# IO_Boardv2_301115.net
KiCad netlist of a schematic drawn in Altium Designer
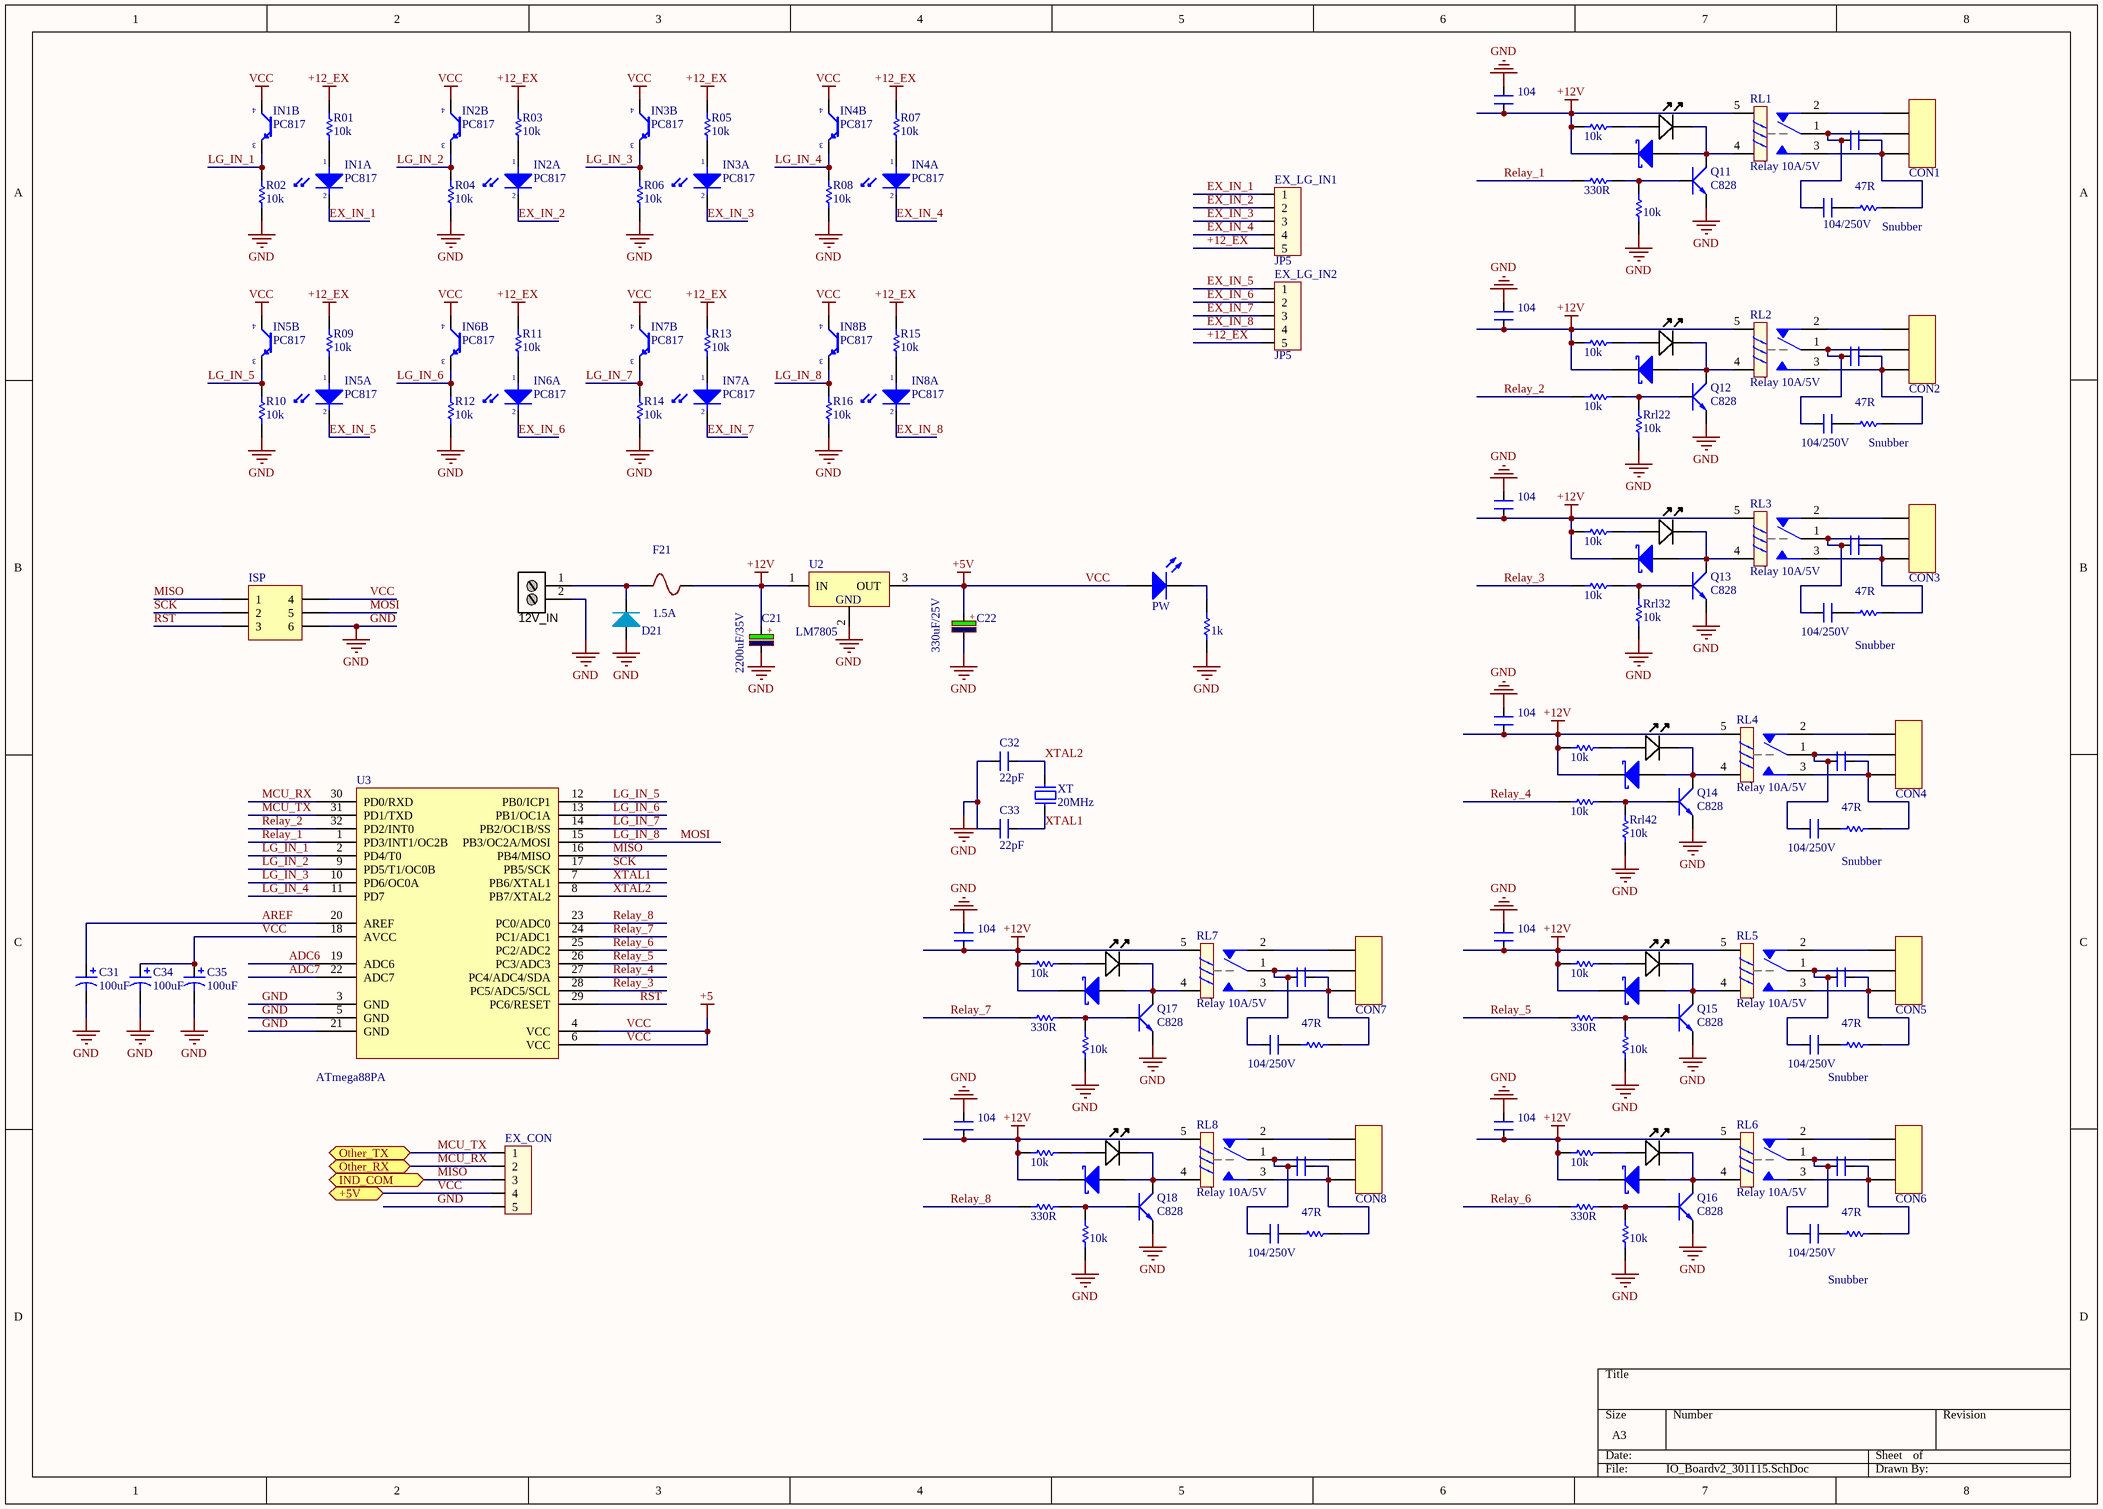
[diagram p0: IO_Boardv2_301115.SchDoc]

(export (version "E")
  (design (tool "Eeschema 10.0.6"))
  (components
    (comp (ref "12V_IN")
      (value "Stackable ScrewTerm")
      (footprint "2P_PCB_ScrewTerm_200mil")
      (description "Terminal Block Screw Type THT 2-Position 3.81mm pitch")
      (libsource (lib "PBL - Connectors") (part "2P_ScrewTerm_90S_3.81MM"))
    )
    (comp (ref "C21")
      (value "2200uF/35V")
      (footprint "heromap:CP_1000uF_25V")
      (description "Cap 1000uF/16V - 220uF/50V")
      (libsource (lib "heromap") (part "CP4"))
    )
    (comp (ref "C22")
      (value "330uF/25V")
      (footprint "heromap:CP1.5/3.4")
      (description "Cap 1000uF/16V - 220uF/50V")
      (libsource (lib "heromap") (part "CP4"))
    )
    (comp (ref "C31")
      (value "100uF")
      (footprint "CAPC2012N_F")
      (fields (field (name "Comment") "Cap"))
      (libsource (lib "Tuan") (part "Cap"))
    )
    (comp (ref "C32")
      (value "22pF")
      (footprint "CAPC1608N")
      (fields (field (name "Comment") "CAP NP"))
      (libsource (lib "Tuan") (part "CAP NP"))
    )
    (comp (ref "C33")
      (value "22pF")
      (footprint "CAPC1608N")
      (fields (field (name "Comment") "CAP NP"))
      (libsource (lib "Tuan") (part "CAP NP"))
    )
    (comp (ref "C34")
      (value "100uF")
      (footprint "CAPC2012N_F")
      (fields (field (name "Comment") "Cap"))
      (libsource (lib "Tuan") (part "Cap"))
    )
    (comp (ref "C35")
      (value "100uF")
      (footprint "CAPC2012N_F")
      (fields (field (name "Comment") "Cap"))
      (libsource (lib "Tuan") (part "Cap"))
    )
    (comp (ref "CON1")
      (value "3P_ScrewTerm_200mil")
      (footprint "3P_ScrewTerm_200mil")
      (libsource (lib "Tuan") (part "3P_ScrewTerm_200mil"))
    )
    (comp (ref "CON2")
      (value "3P_ScrewTerm_200mil")
      (footprint "3P_ScrewTerm_200mil")
      (libsource (lib "Tuan") (part "3P_ScrewTerm_200mil"))
    )
    (comp (ref "CON3")
      (value "3P_ScrewTerm_200mil")
      (footprint "3P_ScrewTerm_200mil")
      (libsource (lib "Tuan") (part "3P_ScrewTerm_200mil"))
    )
    (comp (ref "CON4")
      (value "3P_ScrewTerm_200mil")
      (footprint "3P_ScrewTerm_200mil")
      (libsource (lib "Tuan") (part "3P_ScrewTerm_200mil"))
    )
    (comp (ref "CON5")
      (value "3P_ScrewTerm_200mil")
      (footprint "3P_ScrewTerm_200mil")
      (libsource (lib "Tuan") (part "3P_ScrewTerm_200mil"))
    )
    (comp (ref "CON6")
      (value "3P_ScrewTerm_200mil")
      (footprint "3P_ScrewTerm_200mil")
      (libsource (lib "Tuan") (part "3P_ScrewTerm_200mil"))
    )
    (comp (ref "CON7")
      (value "3P_ScrewTerm_200mil")
      (footprint "3P_ScrewTerm_200mil")
      (libsource (lib "Tuan") (part "3P_ScrewTerm_200mil"))
    )
    (comp (ref "CON8")
      (value "3P_ScrewTerm_200mil")
      (footprint "3P_ScrewTerm_200mil")
      (libsource (lib "Tuan") (part "3P_ScrewTerm_200mil"))
    )
    (comp (ref "Crl1")
      (value "104")
      (footprint "CAPC2012N_F")
      (fields (field (name "Comment") "CAP NP"))
      (libsource (lib "Tuan") (part "CAP NP"))
    )
    (comp (ref "Crl2")
      (value "104")
      (footprint "CAPC2012N_F")
      (fields (field (name "Comment") "CAP NP"))
      (libsource (lib "Tuan") (part "CAP NP"))
    )
    (comp (ref "Crl3")
      (value "104")
      (footprint "CAPC2012N_F")
      (fields (field (name "Comment") "CAP NP"))
      (libsource (lib "Tuan") (part "CAP NP"))
    )
    (comp (ref "Crl4")
      (value "104")
      (footprint "CAPC2012N_F")
      (fields (field (name "Comment") "CAP NP"))
      (libsource (lib "Tuan") (part "CAP NP"))
    )
    (comp (ref "Crl5")
      (value "104")
      (footprint "CAPC2012N_F")
      (fields (field (name "Comment") "CAP NP"))
      (libsource (lib "Tuan") (part "CAP NP"))
    )
    (comp (ref "Crl6")
      (value "104")
      (footprint "CAPC2012N_F")
      (fields (field (name "Comment") "CAP NP"))
      (libsource (lib "Tuan") (part "CAP NP"))
    )
    (comp (ref "Crl7")
      (value "104")
      (footprint "CAPC2012N_F")
      (fields (field (name "Comment") "CAP NP"))
      (libsource (lib "Tuan") (part "CAP NP"))
    )
    (comp (ref "Crl8")
      (value "104")
      (footprint "CAPC2012N_F")
      (fields (field (name "Comment") "CAP NP"))
      (libsource (lib "Tuan") (part "CAP NP"))
    )
    (comp (ref "Csub1")
      (value "104/250V")
      (footprint "CAPMF12.5x4.5x9.0x10mmLS")
      (fields (field (name "Comment") "CAP NP"))
      (libsource (lib "Tuan") (part "CAP NP"))
    )
    (comp (ref "Csub2")
      (value "104/250V")
      (footprint "CAPMF12.5x4.5x9.0x10mmLS")
      (fields (field (name "Comment") "CAP NP"))
      (libsource (lib "Tuan") (part "CAP NP"))
    )
    (comp (ref "Csub3")
      (value "104/250V")
      (footprint "CAPMF12.5x4.5x9.0x10mmLS")
      (fields (field (name "Comment") "CAP NP"))
      (libsource (lib "Tuan") (part "CAP NP"))
    )
    (comp (ref "Csub4")
      (value "104/250V")
      (footprint "CAPMF12.5x4.5x9.0x10mmLS")
      (fields (field (name "Comment") "CAP NP"))
      (libsource (lib "Tuan") (part "CAP NP"))
    )
    (comp (ref "Csub5")
      (value "104/250V")
      (footprint "CAPMF12.5x4.5x9.0x10mmLS")
      (fields (field (name "Comment") "CAP NP"))
      (libsource (lib "Tuan") (part "CAP NP"))
    )
    (comp (ref "Csub6")
      (value "104/250V")
      (footprint "CAPMF12.5x4.5x9.0x10mmLS")
      (fields (field (name "Comment") "CAP NP"))
      (libsource (lib "Tuan") (part "CAP NP"))
    )
    (comp (ref "Csub7")
      (value "104/250V")
      (footprint "CAPMF12.5x4.5x9.0x10mmLS")
      (fields (field (name "Comment") "CAP NP"))
      (libsource (lib "Tuan") (part "CAP NP"))
    )
    (comp (ref "Csub8")
      (value "104/250V")
      (footprint "CAPMF12.5x4.5x9.0x10mmLS")
      (fields (field (name "Comment") "CAP NP"))
      (libsource (lib "Tuan") (part "CAP NP"))
    )
    (comp (ref "D11") (value "Diode") (footprint "DO-214AC") (libsource (lib "Tuan") (part "Diode")))
    (comp (ref "D12") (value "Diode") (footprint "DO-214AC") (libsource (lib "Tuan") (part "Diode")))
    (comp (ref "D13") (value "Diode") (footprint "DO-214AC") (libsource (lib "Tuan") (part "Diode")))
    (comp (ref "D14") (value "Diode") (footprint "DO-214AC") (libsource (lib "Tuan") (part "Diode")))
    (comp (ref "D15") (value "Diode") (footprint "DO-214AC") (libsource (lib "Tuan") (part "Diode")))
    (comp (ref "D16") (value "Diode") (footprint "DO-214AC") (libsource (lib "Tuan") (part "Diode")))
    (comp (ref "D17") (value "Diode") (footprint "DO-214AC") (libsource (lib "Tuan") (part "Diode")))
    (comp (ref "D18") (value "Diode") (footprint "DO-214AC") (libsource (lib "Tuan") (part "Diode")))
    (comp (ref "D21") (value "Diode") (footprint "Diode 3A") (libsource (lib "") (part "Diode_1")))
    (comp (ref "E1")
      (value "Blue")
      (footprint "LED-0805-A")
      (description "LED 0805 SMD Blue 100mcd 470nm")
      (libsource (lib "PBL - Light Sources") (part "LED_SMD_Blue_0805_100mcd"))
    )
    (comp (ref "E2")
      (value "Blue")
      (footprint "LED-0805-A")
      (description "LED 0805 SMD Blue 100mcd 470nm")
      (libsource (lib "PBL - Light Sources") (part "LED_SMD_Blue_0805_100mcd"))
    )
    (comp (ref "E3")
      (value "Blue")
      (footprint "LED-0805-A")
      (description "LED 0805 SMD Blue 100mcd 470nm")
      (libsource (lib "PBL - Light Sources") (part "LED_SMD_Blue_0805_100mcd"))
    )
    (comp (ref "E4")
      (value "Blue")
      (footprint "LED-0805-A")
      (description "LED 0805 SMD Blue 100mcd 470nm")
      (libsource (lib "PBL - Light Sources") (part "LED_SMD_Blue_0805_100mcd"))
    )
    (comp (ref "E5")
      (value "Blue")
      (footprint "LED-0805-A")
      (description "LED 0805 SMD Blue 100mcd 470nm")
      (libsource (lib "PBL - Light Sources") (part "LED_SMD_Blue_0805_100mcd"))
    )
    (comp (ref "E6")
      (value "Blue")
      (footprint "LED-0805-A")
      (description "LED 0805 SMD Blue 100mcd 470nm")
      (libsource (lib "PBL - Light Sources") (part "LED_SMD_Blue_0805_100mcd"))
    )
    (comp (ref "E7")
      (value "Blue")
      (footprint "LED-0805-A")
      (description "LED 0805 SMD Blue 100mcd 470nm")
      (libsource (lib "PBL - Light Sources") (part "LED_SMD_Blue_0805_100mcd"))
    )
    (comp (ref "E8")
      (value "Blue")
      (footprint "LED-0805-A")
      (description "LED 0805 SMD Blue 100mcd 470nm")
      (libsource (lib "PBL - Light Sources") (part "LED_SMD_Blue_0805_100mcd"))
    )
    (comp (ref "EX_CON")
      (value "JP5")
      (footprint "heromap:CON5")
      (description "Connector 5")
      (libsource (lib "heromap") (part "Con5"))
    )
    (comp (ref "EX_LG_IN1")
      (value "JP5")
      (footprint "heromap:CON5")
      (description "Connector 5")
      (libsource (lib "heromap") (part "Con5"))
    )
    (comp (ref "EX_LG_IN2")
      (value "JP5")
      (footprint "heromap:CON5")
      (description "Connector 5")
      (libsource (lib "heromap") (part "Con5"))
    )
    (comp (ref "F21") (value "1.5A") (footprint "FUSE_SR-5-BK") (libsource (lib "Tuan") (part "Fuse")))
    (comp (ref "IN1") (value "PC817") (footprint "DIP4/W0.3") (libsource (lib "Tuan") (part "Opto")))
    (comp (ref "IN2") (value "PC817") (footprint "DIP4/W0.3") (libsource (lib "Tuan") (part "Opto")))
    (comp (ref "IN3") (value "PC817") (footprint "DIP4/W0.3") (libsource (lib "Tuan") (part "Opto")))
    (comp (ref "IN4") (value "PC817") (footprint "DIP4/W0.3") (libsource (lib "Tuan") (part "Opto")))
    (comp (ref "IN5") (value "PC817") (footprint "DIP4/W0.3") (libsource (lib "Tuan") (part "Opto")))
    (comp (ref "IN6") (value "PC817") (footprint "DIP4/W0.3") (libsource (lib "Tuan") (part "Opto")))
    (comp (ref "IN7") (value "PC817") (footprint "DIP4/W0.3") (libsource (lib "Tuan") (part "Opto")))
    (comp (ref "IN8") (value "PC817") (footprint "DIP4/W0.3") (libsource (lib "Tuan") (part "Opto")))
    (comp (ref "ISP")
      (value "Header 3X2A")
      (footprint "HDR2X3_CEN")
      (description "Header, 3-Pin, Dual row")
      (fields (field (name "PUBLISHER") "Altium Limited"))
      (libsource (lib "Miscellaneous Connectors") (part "Header 3X2A"))
    )
    (comp (ref "MOV1")
      (value "CAP NP")
      (footprint "CAPC500P450250X550")
      (libsource (lib "Tuan") (part "CAP NP"))
    )
    (comp (ref "MOV2")
      (value "CAP NP")
      (footprint "CAPC500P450250X550")
      (libsource (lib "Tuan") (part "CAP NP"))
    )
    (comp (ref "MOV3")
      (value "CAP NP")
      (footprint "CAPC500P450250X550")
      (libsource (lib "Tuan") (part "CAP NP"))
    )
    (comp (ref "MOV4")
      (value "CAP NP")
      (footprint "CAPC500P450250X550")
      (libsource (lib "Tuan") (part "CAP NP"))
    )
    (comp (ref "MOV5")
      (value "CAP NP")
      (footprint "CAPC500P450250X550")
      (libsource (lib "Tuan") (part "CAP NP"))
    )
    (comp (ref "MOV6")
      (value "CAP NP")
      (footprint "CAPC500P450250X550")
      (libsource (lib "Tuan") (part "CAP NP"))
    )
    (comp (ref "MOV7")
      (value "CAP NP")
      (footprint "CAPC500P450250X550")
      (libsource (lib "Tuan") (part "CAP NP"))
    )
    (comp (ref "MOV8")
      (value "CAP NP")
      (footprint "CAPC500P450250X550")
      (libsource (lib "Tuan") (part "CAP NP"))
    )
    (comp (ref "PW") (value "Led") (footprint "LED 5mm RED") (libsource (lib "Tuan") (part "Led")))
    (comp (ref "Q11")
      (value "C828")
      (footprint "SOT23 TOP")
      (description "Transistor C828 C1815....")
      (libsource (lib "Tuan") (part "NPN"))
    )
    (comp (ref "Q12")
      (value "C828")
      (footprint "SOT23 TOP")
      (description "Transistor C828 C1815....")
      (libsource (lib "Tuan") (part "NPN"))
    )
    (comp (ref "Q13")
      (value "C828")
      (footprint "SOT23 TOP")
      (description "Transistor C828 C1815....")
      (libsource (lib "Tuan") (part "NPN"))
    )
    (comp (ref "Q14")
      (value "C828")
      (footprint "SOT23 TOP")
      (description "Transistor C828 C1815....")
      (libsource (lib "Tuan") (part "NPN"))
    )
    (comp (ref "Q15")
      (value "C828")
      (footprint "SOT23 TOP")
      (description "Transistor C828 C1815....")
      (libsource (lib "Tuan") (part "NPN"))
    )
    (comp (ref "Q16")
      (value "C828")
      (footprint "SOT23 TOP")
      (description "Transistor C828 C1815....")
      (libsource (lib "Tuan") (part "NPN"))
    )
    (comp (ref "Q17")
      (value "C828")
      (footprint "SOT23 TOP")
      (description "Transistor C828 C1815....")
      (libsource (lib "Tuan") (part "NPN"))
    )
    (comp (ref "Q18")
      (value "C828")
      (footprint "SOT23 TOP")
      (description "Transistor C828 C1815....")
      (libsource (lib "Tuan") (part "NPN"))
    )
    (comp (ref "R01")
      (value "10k")
      (footprint "RESC2012N_F")
      (fields (field (name "Comment") "Res"))
      (libsource (lib "Tuan") (part "Res"))
    )
    (comp (ref "R02")
      (value "10k")
      (footprint "RESC2012N_F")
      (fields (field (name "Comment") "Res"))
      (libsource (lib "Tuan") (part "Res"))
    )
    (comp (ref "R03")
      (value "10k")
      (footprint "RESC2012N_F")
      (fields (field (name "Comment") "Res"))
      (libsource (lib "Tuan") (part "Res"))
    )
    (comp (ref "R04")
      (value "10k")
      (footprint "RESC2012N_F")
      (fields (field (name "Comment") "Res"))
      (libsource (lib "Tuan") (part "Res"))
    )
    (comp (ref "R05")
      (value "10k")
      (footprint "RESC2012N_F")
      (fields (field (name "Comment") "Res"))
      (libsource (lib "Tuan") (part "Res"))
    )
    (comp (ref "R06")
      (value "10k")
      (footprint "RESC2012N_F")
      (fields (field (name "Comment") "Res"))
      (libsource (lib "Tuan") (part "Res"))
    )
    (comp (ref "R07")
      (value "10k")
      (footprint "RESC2012N_F")
      (fields (field (name "Comment") "Res"))
      (libsource (lib "Tuan") (part "Res"))
    )
    (comp (ref "R08")
      (value "10k")
      (footprint "RESC2012N_F")
      (fields (field (name "Comment") "Res"))
      (libsource (lib "Tuan") (part "Res"))
    )
    (comp (ref "R09")
      (value "10k")
      (footprint "RESC2012N_F")
      (fields (field (name "Comment") "Res"))
      (libsource (lib "Tuan") (part "Res"))
    )
    (comp (ref "R10")
      (value "10k")
      (footprint "RESC2012N_F")
      (fields (field (name "Comment") "Res"))
      (libsource (lib "Tuan") (part "Res"))
    )
    (comp (ref "R11")
      (value "10k")
      (footprint "RESC2012N_F")
      (fields (field (name "Comment") "Res"))
      (libsource (lib "Tuan") (part "Res"))
    )
    (comp (ref "R12")
      (value "10k")
      (footprint "RESC2012N_F")
      (fields (field (name "Comment") "Res"))
      (libsource (lib "Tuan") (part "Res"))
    )
    (comp (ref "R13")
      (value "10k")
      (footprint "RESC2012N_F")
      (fields (field (name "Comment") "Res"))
      (libsource (lib "Tuan") (part "Res"))
    )
    (comp (ref "R14")
      (value "10k")
      (footprint "RESC2012N_F")
      (fields (field (name "Comment") "Res"))
      (libsource (lib "Tuan") (part "Res"))
    )
    (comp (ref "R15")
      (value "10k")
      (footprint "RESC2012N_F")
      (fields (field (name "Comment") "Res"))
      (libsource (lib "Tuan") (part "Res"))
    )
    (comp (ref "R16")
      (value "10k")
      (footprint "RESC2012N_F")
      (fields (field (name "Comment") "Res"))
      (libsource (lib "Tuan") (part "Res"))
    )
    (comp (ref "R21")
      (value "1k")
      (footprint "RESC2012N_F")
      (fields (field (name "Comment") "Res_0805_1k"))
      (libsource (lib "Tuan") (part "Res"))
    )
    (comp (ref "RL1")
      (value "Relay 10A/5V")
      (footprint "RL_5PIN")
      (description "Relay SPDT,10A - 12VDC 5 Pin")
      (libsource (lib "syhaunguyen") (part "Relay 1"))
    )
    (comp (ref "RL2")
      (value "Relay 10A/5V")
      (footprint "RL_5PIN")
      (description "Relay SPDT,10A - 12VDC 5 Pin")
      (libsource (lib "syhaunguyen") (part "Relay 1"))
    )
    (comp (ref "RL3")
      (value "Relay 10A/5V")
      (footprint "RL_5PIN")
      (description "Relay SPDT,10A - 12VDC 5 Pin")
      (libsource (lib "syhaunguyen") (part "Relay 1"))
    )
    (comp (ref "RL4")
      (value "Relay 10A/5V")
      (footprint "RL_5PIN")
      (description "Relay SPDT,10A - 12VDC 5 Pin")
      (libsource (lib "syhaunguyen") (part "Relay 1"))
    )
    (comp (ref "RL5")
      (value "Relay 10A/5V")
      (footprint "RL_5PIN")
      (description "Relay SPDT,10A - 12VDC 5 Pin")
      (libsource (lib "syhaunguyen") (part "Relay 1"))
    )
    (comp (ref "RL6")
      (value "Relay 10A/5V")
      (footprint "RL_5PIN")
      (description "Relay SPDT,10A - 12VDC 5 Pin")
      (libsource (lib "syhaunguyen") (part "Relay 1"))
    )
    (comp (ref "RL7")
      (value "Relay 10A/5V")
      (footprint "RL_5PIN")
      (description "Relay SPDT,10A - 12VDC 5 Pin")
      (libsource (lib "syhaunguyen") (part "Relay 1"))
    )
    (comp (ref "RL8")
      (value "Relay 10A/5V")
      (footprint "RL_5PIN")
      (description "Relay SPDT,10A - 12VDC 5 Pin")
      (libsource (lib "syhaunguyen") (part "Relay 1"))
    )
    (comp (ref "Rl52")
      (value "10k")
      (footprint "RESC1608N_ZERO")
      (fields (field (name "Comment") "Res"))
      (libsource (lib "Tuan") (part "Res"))
    )
    (comp (ref "Rrl11")
      (value "330R")
      (footprint "RESC1608N_ZERO")
      (fields (field (name "Comment") "Res"))
      (libsource (lib "Tuan") (part "Res"))
    )
    (comp (ref "Rrl12")
      (value "10k")
      (footprint "RESC1608N_ZERO")
      (fields (field (name "Comment") "Res"))
      (libsource (lib "Tuan") (part "Res"))
    )
    (comp (ref "Rrl13")
      (value "10k")
      (footprint "RESC1608N_ZERO")
      (fields (field (name "Comment") "Res"))
      (libsource (lib "Tuan") (part "Res"))
    )
    (comp (ref "Rrl21")
      (value "10k")
      (footprint "RESC1608N_ZERO")
      (fields (field (name "Comment") "Res"))
      (libsource (lib "Tuan") (part "Res"))
    )
    (comp (ref "Rrl22")
      (value "10k")
      (footprint "RESC1608N_ZERO")
      (fields (field (name "Comment") "Res"))
      (libsource (lib "Tuan") (part "Res"))
    )
    (comp (ref "Rrl23")
      (value "10k")
      (footprint "RESC1608N_ZERO")
      (fields (field (name "Comment") "Res"))
      (libsource (lib "Tuan") (part "Res"))
    )
    (comp (ref "Rrl31")
      (value "10k")
      (footprint "RESC1608N_ZERO")
      (fields (field (name "Comment") "Res"))
      (libsource (lib "Tuan") (part "Res"))
    )
    (comp (ref "Rrl32")
      (value "10k")
      (footprint "RESC1608N_ZERO")
      (fields (field (name "Comment") "Res"))
      (libsource (lib "Tuan") (part "Res"))
    )
    (comp (ref "Rrl33")
      (value "10k")
      (footprint "RESC1608N_ZERO")
      (fields (field (name "Comment") "Res"))
      (libsource (lib "Tuan") (part "Res"))
    )
    (comp (ref "Rrl41")
      (value "10k")
      (footprint "RESC1608N_ZERO")
      (fields (field (name "Comment") "Res"))
      (libsource (lib "Tuan") (part "Res"))
    )
    (comp (ref "Rrl42")
      (value "10k")
      (footprint "RESC1608N_ZERO")
      (fields (field (name "Comment") "Res"))
      (libsource (lib "Tuan") (part "Res"))
    )
    (comp (ref "Rrl43")
      (value "10k")
      (footprint "RESC1608N_ZERO")
      (fields (field (name "Comment") "Res"))
      (libsource (lib "Tuan") (part "Res"))
    )
    (comp (ref "Rrl51")
      (value "330R")
      (footprint "RESC1608N_ZERO")
      (fields (field (name "Comment") "Res"))
      (libsource (lib "Tuan") (part "Res"))
    )
    (comp (ref "Rrl53")
      (value "10k")
      (footprint "RESC1608N_ZERO")
      (fields (field (name "Comment") "Res"))
      (libsource (lib "Tuan") (part "Res"))
    )
    (comp (ref "Rrl61")
      (value "330R")
      (footprint "RESC1608N_ZERO")
      (fields (field (name "Comment") "Res"))
      (libsource (lib "Tuan") (part "Res"))
    )
    (comp (ref "Rrl62")
      (value "10k")
      (footprint "RESC1608N_ZERO")
      (fields (field (name "Comment") "Res"))
      (libsource (lib "Tuan") (part "Res"))
    )
    (comp (ref "Rrl63")
      (value "10k")
      (footprint "RESC1608N_ZERO")
      (fields (field (name "Comment") "Res"))
      (libsource (lib "Tuan") (part "Res"))
    )
    (comp (ref "Rrl71")
      (value "330R")
      (footprint "RESC1608N_ZERO")
      (fields (field (name "Comment") "Res"))
      (libsource (lib "Tuan") (part "Res"))
    )
    (comp (ref "Rrl72")
      (value "10k")
      (footprint "RESC1608N_ZERO")
      (fields (field (name "Comment") "Res"))
      (libsource (lib "Tuan") (part "Res"))
    )
    (comp (ref "Rrl73")
      (value "10k")
      (footprint "RESC1608N_ZERO")
      (fields (field (name "Comment") "Res"))
      (libsource (lib "Tuan") (part "Res"))
    )
    (comp (ref "Rrl81")
      (value "330R")
      (footprint "RESC1608N_ZERO")
      (fields (field (name "Comment") "Res"))
      (libsource (lib "Tuan") (part "Res"))
    )
    (comp (ref "Rrl82")
      (value "10k")
      (footprint "RESC1608N_ZERO")
      (fields (field (name "Comment") "Res"))
      (libsource (lib "Tuan") (part "Res"))
    )
    (comp (ref "Rrl83")
      (value "10k")
      (footprint "RESC1608N_ZERO")
      (fields (field (name "Comment") "Res"))
      (libsource (lib "Tuan") (part "Res"))
    )
    (comp (ref "Rsub1")
      (value "47R")
      (footprint "RESTH_AXIAL-0.4")
      (fields (field (name "Comment") "Res"))
      (libsource (lib "Tuan") (part "Res"))
    )
    (comp (ref "Rsub2")
      (value "47R")
      (footprint "RESTH_AXIAL-0.4")
      (fields (field (name "Comment") "Res"))
      (libsource (lib "Tuan") (part "Res"))
    )
    (comp (ref "Rsub3")
      (value "47R")
      (footprint "RESTH_AXIAL-0.4")
      (fields (field (name "Comment") "Res"))
      (libsource (lib "Tuan") (part "Res"))
    )
    (comp (ref "Rsub4")
      (value "47R")
      (footprint "RESTH_AXIAL-0.4")
      (fields (field (name "Comment") "Res"))
      (libsource (lib "Tuan") (part "Res"))
    )
    (comp (ref "Rsub5")
      (value "47R")
      (footprint "RESTH_AXIAL-0.4")
      (fields (field (name "Comment") "Res"))
      (libsource (lib "Tuan") (part "Res"))
    )
    (comp (ref "Rsub6")
      (value "47R")
      (footprint "RESTH_AXIAL-0.4")
      (fields (field (name "Comment") "Res"))
      (libsource (lib "Tuan") (part "Res"))
    )
    (comp (ref "Rsub7")
      (value "47R")
      (footprint "RESTH_AXIAL-0.4")
      (fields (field (name "Comment") "Res"))
      (libsource (lib "Tuan") (part "Res"))
    )
    (comp (ref "Rsub8")
      (value "47R")
      (footprint "RESTH_AXIAL-0.4")
      (fields (field (name "Comment") "Res"))
      (libsource (lib "Tuan") (part "Res"))
    )
    (comp (ref "U2") (value "LM7805") (footprint "TO-220") (libsource (lib "Tuan") (part "LM78xx")))
    (comp (ref "U3")
      (value "ATmega88PA")
      (footprint "32PIN")
      (description "ATmega48/168/328")
      (libsource (lib "Tuan") (part "ATmega48/168/328"))
    )
    (comp (ref "XT") (value "20MHz") (footprint "XT2") (libsource (lib "Tuan") (part "Crystal")))
  )
  (nets
    (net (code "1") (name "+5") (class "Default")
      (node (ref "C22") (pin "1") (pinfunction "1_1") (pintype "passive"))
      (node (ref "C34") (pin "1") (pinfunction "1_1") (pintype "passive"))
      (node (ref "C35") (pin "1") (pinfunction "1_1") (pintype "passive"))
      (node (ref "EX_CON") (pin "4") (pinfunction "4_4") (pintype "passive"))
      (node (ref "IN1") (pin "4") (pinfunction "C_4") (pintype "passive"))
      (node (ref "IN2") (pin "4") (pinfunction "C_4") (pintype "passive"))
      (node (ref "IN3") (pin "4") (pinfunction "C_4") (pintype "passive"))
      (node (ref "IN4") (pin "4") (pinfunction "C_4") (pintype "passive"))
      (node (ref "IN5") (pin "4") (pinfunction "C_4") (pintype "passive"))
      (node (ref "IN6") (pin "4") (pinfunction "C_4") (pintype "passive"))
      (node (ref "IN7") (pin "4") (pinfunction "C_4") (pintype "passive"))
      (node (ref "IN8") (pin "4") (pinfunction "C_4") (pintype "passive"))
      (node (ref "ISP") (pin "4") (pinfunction "4_4") (pintype "passive"))
      (node (ref "PW") (pin "1") (pinfunction "A_1") (pintype "passive"))
      (node (ref "U2") (pin "3") (pinfunction "OUT_3") (pintype "passive"))
      (node (ref "U3") (pin "18") (pinfunction "AVCC_18") (pintype "passive"))
      (node (ref "U3") (pin "4") (pinfunction "VCC_4") (pintype "passive"))
      (node (ref "U3") (pin "6") (pinfunction "VCC_6") (pintype "passive"))
    )
    (net (code "2") (name "+12V") (class "Default")
      (node (ref "C21") (pin "1") (pinfunction "1_1") (pintype "passive"))
      (node (ref "Crl1") (pin "1") (pinfunction "1_1") (pintype "passive"))
      (node (ref "Crl2") (pin "1") (pinfunction "1_1") (pintype "passive"))
      (node (ref "Crl3") (pin "1") (pinfunction "1_1") (pintype "passive"))
      (node (ref "Crl4") (pin "1") (pinfunction "1_1") (pintype "passive"))
      (node (ref "Crl5") (pin "1") (pinfunction "1_1") (pintype "passive"))
      (node (ref "Crl6") (pin "1") (pinfunction "1_1") (pintype "passive"))
      (node (ref "Crl7") (pin "1") (pinfunction "1_1") (pintype "passive"))
      (node (ref "Crl8") (pin "1") (pinfunction "1_1") (pintype "passive"))
      (node (ref "D11") (pin "2") (pinfunction "K_2") (pintype "passive"))
      (node (ref "D12") (pin "2") (pinfunction "K_2") (pintype "passive"))
      (node (ref "D13") (pin "2") (pinfunction "K_2") (pintype "passive"))
      (node (ref "D14") (pin "2") (pinfunction "K_2") (pintype "passive"))
      (node (ref "D15") (pin "2") (pinfunction "K_2") (pintype "passive"))
      (node (ref "D16") (pin "2") (pinfunction "K_2") (pintype "passive"))
      (node (ref "D17") (pin "2") (pinfunction "K_2") (pintype "passive"))
      (node (ref "D18") (pin "2") (pinfunction "K_2") (pintype "passive"))
      (node (ref "F21") (pin "2") (pinfunction "2_2") (pintype "passive"))
      (node (ref "RL1") (pin "5") (pinfunction "5_5") (pintype "passive"))
      (node (ref "RL2") (pin "5") (pinfunction "5_5") (pintype "passive"))
      (node (ref "RL3") (pin "5") (pinfunction "5_5") (pintype "passive"))
      (node (ref "RL4") (pin "5") (pinfunction "5_5") (pintype "passive"))
      (node (ref "RL5") (pin "5") (pinfunction "5_5") (pintype "passive"))
      (node (ref "RL6") (pin "5") (pinfunction "5_5") (pintype "passive"))
      (node (ref "RL7") (pin "5") (pinfunction "5_5") (pintype "passive"))
      (node (ref "RL8") (pin "5") (pinfunction "5_5") (pintype "passive"))
      (node (ref "Rrl13") (pin "2") (pinfunction "2_2") (pintype "passive"))
      (node (ref "Rrl23") (pin "2") (pinfunction "2_2") (pintype "passive"))
      (node (ref "Rrl33") (pin "2") (pinfunction "2_2") (pintype "passive"))
      (node (ref "Rrl43") (pin "2") (pinfunction "2_2") (pintype "passive"))
      (node (ref "Rrl53") (pin "2") (pinfunction "2_2") (pintype "passive"))
      (node (ref "Rrl63") (pin "2") (pinfunction "2_2") (pintype "passive"))
      (node (ref "Rrl73") (pin "2") (pinfunction "2_2") (pintype "passive"))
      (node (ref "Rrl83") (pin "2") (pinfunction "2_2") (pintype "passive"))
      (node (ref "U2") (pin "1") (pinfunction "IN_1") (pintype "passive"))
    )
    (net (code "3") (name "+12_EX") (class "Default")
      (node (ref "EX_LG_IN1") (pin "5") (pinfunction "5_5") (pintype "passive"))
      (node (ref "EX_LG_IN2") (pin "5") (pinfunction "5_5") (pintype "passive"))
      (node (ref "R01") (pin "2") (pinfunction "2_2") (pintype "passive"))
      (node (ref "R03") (pin "2") (pinfunction "2_2") (pintype "passive"))
      (node (ref "R05") (pin "2") (pinfunction "2_2") (pintype "passive"))
      (node (ref "R07") (pin "2") (pinfunction "2_2") (pintype "passive"))
      (node (ref "R09") (pin "2") (pinfunction "2_2") (pintype "passive"))
      (node (ref "R11") (pin "2") (pinfunction "2_2") (pintype "passive"))
      (node (ref "R13") (pin "2") (pinfunction "2_2") (pintype "passive"))
      (node (ref "R15") (pin "2") (pinfunction "2_2") (pintype "passive"))
    )
    (net (code "4") (name "/ADC6") (class "Default")
      (node (ref "U3") (pin "19") (pinfunction "ADC6_19") (pintype "passive"))
    )
    (net (code "5") (name "/ADC7") (class "Default")
      (node (ref "U3") (pin "22") (pinfunction "ADC7_22") (pintype "passive"))
    )
    (net (code "6") (name "/AREF") (class "Default")
      (node (ref "C31") (pin "1") (pinfunction "1_1") (pintype "passive"))
      (node (ref "U3") (pin "20") (pinfunction "AREF_20") (pintype "passive"))
    )
    (net (code "7") (name "/EX_IN_1") (class "Default")
      (node (ref "EX_LG_IN1") (pin "1") (pinfunction "1_1") (pintype "passive"))
      (node (ref "IN1") (pin "2") (pinfunction "K_2") (pintype "passive"))
    )
    (net (code "8") (name "/EX_IN_2") (class "Default")
      (node (ref "EX_LG_IN1") (pin "2") (pinfunction "2_2") (pintype "passive"))
      (node (ref "IN2") (pin "2") (pinfunction "K_2") (pintype "passive"))
    )
    (net (code "9") (name "/EX_IN_3") (class "Default")
      (node (ref "EX_LG_IN1") (pin "3") (pinfunction "3_3") (pintype "passive"))
      (node (ref "IN3") (pin "2") (pinfunction "K_2") (pintype "passive"))
    )
    (net (code "10") (name "/EX_IN_4") (class "Default")
      (node (ref "EX_LG_IN1") (pin "4") (pinfunction "4_4") (pintype "passive"))
      (node (ref "IN4") (pin "2") (pinfunction "K_2") (pintype "passive"))
    )
    (net (code "11") (name "/EX_IN_5") (class "Default")
      (node (ref "EX_LG_IN2") (pin "1") (pinfunction "1_1") (pintype "passive"))
      (node (ref "IN5") (pin "2") (pinfunction "K_2") (pintype "passive"))
    )
    (net (code "12") (name "/EX_IN_6") (class "Default")
      (node (ref "EX_LG_IN2") (pin "2") (pinfunction "2_2") (pintype "passive"))
      (node (ref "IN6") (pin "2") (pinfunction "K_2") (pintype "passive"))
    )
    (net (code "13") (name "/EX_IN_7") (class "Default")
      (node (ref "EX_LG_IN2") (pin "3") (pinfunction "3_3") (pintype "passive"))
      (node (ref "IN7") (pin "2") (pinfunction "K_2") (pintype "passive"))
    )
    (net (code "14") (name "/EX_IN_8") (class "Default")
      (node (ref "EX_LG_IN2") (pin "4") (pinfunction "4_4") (pintype "passive"))
      (node (ref "IN8") (pin "2") (pinfunction "K_2") (pintype "passive"))
    )
    (net (code "15") (name "/LG_IN_1") (class "Default")
      (node (ref "IN1") (pin "3") (pinfunction "E_3") (pintype "passive"))
      (node (ref "R02") (pin "2") (pinfunction "2_2") (pintype "passive"))
      (node (ref "U3") (pin "2") (pinfunction "PD4/T0_2") (pintype "passive"))
    )
    (net (code "16") (name "/LG_IN_2") (class "Default")
      (node (ref "IN2") (pin "3") (pinfunction "E_3") (pintype "passive"))
      (node (ref "R04") (pin "2") (pinfunction "2_2") (pintype "passive"))
      (node (ref "U3") (pin "9") (pinfunction "PD5/T1/OC0B_9") (pintype "passive"))
    )
    (net (code "17") (name "/LG_IN_3") (class "Default")
      (node (ref "IN3") (pin "3") (pinfunction "E_3") (pintype "passive"))
      (node (ref "R06") (pin "2") (pinfunction "2_2") (pintype "passive"))
      (node (ref "U3") (pin "10") (pinfunction "PD6/OC0A_10") (pintype "passive"))
    )
    (net (code "18") (name "/LG_IN_4") (class "Default")
      (node (ref "IN4") (pin "3") (pinfunction "E_3") (pintype "passive"))
      (node (ref "R08") (pin "2") (pinfunction "2_2") (pintype "passive"))
      (node (ref "U3") (pin "11") (pinfunction "PD7_11") (pintype "passive"))
    )
    (net (code "19") (name "/LG_IN_5") (class "Default")
      (node (ref "IN5") (pin "3") (pinfunction "E_3") (pintype "passive"))
      (node (ref "R10") (pin "2") (pinfunction "2_2") (pintype "passive"))
      (node (ref "U3") (pin "12") (pinfunction "PB0/ICP1_12") (pintype "passive"))
    )
    (net (code "20") (name "/LG_IN_6") (class "Default")
      (node (ref "IN6") (pin "3") (pinfunction "E_3") (pintype "passive"))
      (node (ref "R12") (pin "2") (pinfunction "2_2") (pintype "passive"))
      (node (ref "U3") (pin "13") (pinfunction "PB1/OC1A_13") (pintype "passive"))
    )
    (net (code "21") (name "/LG_IN_7") (class "Default")
      (node (ref "IN7") (pin "3") (pinfunction "E_3") (pintype "passive"))
      (node (ref "R14") (pin "2") (pinfunction "2_2") (pintype "passive"))
      (node (ref "U3") (pin "14") (pinfunction "PB2/OC1B/SS_14") (pintype "passive"))
    )
    (net (code "22") (name "/LG_IN_8") (class "Default")
      (node (ref "IN8") (pin "3") (pinfunction "E_3") (pintype "passive"))
      (node (ref "ISP") (pin "5") (pinfunction "5_5") (pintype "passive"))
      (node (ref "R16") (pin "2") (pinfunction "2_2") (pintype "passive"))
      (node (ref "U3") (pin "15") (pinfunction "PB3/OC2A/MOSI_15") (pintype "passive"))
    )
    (net (code "23") (name "/MCU_RX") (class "Default")
      (node (ref "EX_CON") (pin "2") (pinfunction "2_2") (pintype "passive"))
      (node (ref "U3") (pin "30") (pinfunction "PD0/RXD_30") (pintype "passive"))
    )
    (net (code "24") (name "/MCU_TX") (class "Default")
      (node (ref "EX_CON") (pin "1") (pinfunction "1_1") (pintype "passive"))
      (node (ref "U3") (pin "31") (pinfunction "PD1/TXD_31") (pintype "passive"))
    )
    (net (code "25") (name "/MISO") (class "Default")
      (node (ref "EX_CON") (pin "3") (pinfunction "3_3") (pintype "passive"))
      (node (ref "ISP") (pin "1") (pinfunction "1_1") (pintype "passive"))
      (node (ref "U3") (pin "16") (pinfunction "PB4/MISO_16") (pintype "passive"))
    )
    (net (code "26") (name "/RST") (class "Default")
      (node (ref "ISP") (pin "3") (pinfunction "3_3") (pintype "passive"))
      (node (ref "U3") (pin "29") (pinfunction "PC6/RESET_29") (pintype "passive"))
    )
    (net (code "27") (name "/Relay_1") (class "Default")
      (node (ref "Rrl11") (pin "1") (pinfunction "1_1") (pintype "passive"))
      (node (ref "U3") (pin "1") (pinfunction "PD3/INT1/OC2B_1") (pintype "passive"))
    )
    (net (code "28") (name "/Relay_2") (class "Default")
      (node (ref "Rrl21") (pin "1") (pinfunction "1_1") (pintype "passive"))
      (node (ref "U3") (pin "32") (pinfunction "PD2/INT0_32") (pintype "passive"))
    )
    (net (code "29") (name "/Relay_3") (class "Default")
      (node (ref "Rrl31") (pin "1") (pinfunction "1_1") (pintype "passive"))
      (node (ref "U3") (pin "28") (pinfunction "PC5/ADC5/SCL_28") (pintype "passive"))
    )
    (net (code "30") (name "/Relay_4") (class "Default")
      (node (ref "Rrl41") (pin "1") (pinfunction "1_1") (pintype "passive"))
      (node (ref "U3") (pin "27") (pinfunction "PC4/ADC4/SDA_27") (pintype "passive"))
    )
    (net (code "31") (name "/Relay_5") (class "Default")
      (node (ref "Rrl51") (pin "1") (pinfunction "1_1") (pintype "passive"))
      (node (ref "U3") (pin "26") (pinfunction "PC3/ADC3_26") (pintype "passive"))
    )
    (net (code "32") (name "/Relay_6") (class "Default")
      (node (ref "Rrl61") (pin "1") (pinfunction "1_1") (pintype "passive"))
      (node (ref "U3") (pin "25") (pinfunction "PC2/ADC2_25") (pintype "passive"))
    )
    (net (code "33") (name "/Relay_7") (class "Default")
      (node (ref "Rrl71") (pin "1") (pinfunction "1_1") (pintype "passive"))
      (node (ref "U3") (pin "24") (pinfunction "PC1/ADC1_24") (pintype "passive"))
    )
    (net (code "34") (name "/Relay_8") (class "Default")
      (node (ref "Rrl81") (pin "1") (pinfunction "1_1") (pintype "passive"))
      (node (ref "U3") (pin "23") (pinfunction "PC0/ADC0_23") (pintype "passive"))
    )
    (net (code "35") (name "/SCK") (class "Default")
      (node (ref "ISP") (pin "2") (pinfunction "2_2") (pintype "passive"))
      (node (ref "U3") (pin "17") (pinfunction "PB5/SCK_17") (pintype "passive"))
    )
    (net (code "36") (name "/XTAL1") (class "Default")
      (node (ref "C33") (pin "1") (pinfunction "1_1") (pintype "passive"))
      (node (ref "U3") (pin "7") (pinfunction "PB6/XTAL1_7") (pintype "passive"))
      (node (ref "XT") (pin "1") (pinfunction "1_1") (pintype "passive"))
    )
    (net (code "37") (name "/XTAL2") (class "Default")
      (node (ref "C32") (pin "1") (pinfunction "1_1") (pintype "passive"))
      (node (ref "U3") (pin "8") (pinfunction "PB7/XTAL2_8") (pintype "passive"))
      (node (ref "XT") (pin "2") (pinfunction "2_2") (pintype "passive"))
    )
    (net (code "38") (name "GND") (class "Default")
      (node (ref "12V_IN") (pin "2") (pinfunction "2_2") (pintype "passive"))
      (node (ref "C21") (pin "2") (pinfunction "2_2") (pintype "passive"))
      (node (ref "C22") (pin "2") (pinfunction "2_2") (pintype "passive"))
      (node (ref "C31") (pin "2") (pinfunction "2_2") (pintype "passive"))
      (node (ref "C32") (pin "2") (pinfunction "2_2") (pintype "passive"))
      (node (ref "C33") (pin "2") (pinfunction "2_2") (pintype "passive"))
      (node (ref "C34") (pin "2") (pinfunction "2_2") (pintype "passive"))
      (node (ref "C35") (pin "2") (pinfunction "2_2") (pintype "passive"))
      (node (ref "Crl1") (pin "2") (pinfunction "2_2") (pintype "passive"))
      (node (ref "Crl2") (pin "2") (pinfunction "2_2") (pintype "passive"))
      (node (ref "Crl3") (pin "2") (pinfunction "2_2") (pintype "passive"))
      (node (ref "Crl4") (pin "2") (pinfunction "2_2") (pintype "passive"))
      (node (ref "Crl5") (pin "2") (pinfunction "2_2") (pintype "passive"))
      (node (ref "Crl6") (pin "2") (pinfunction "2_2") (pintype "passive"))
      (node (ref "Crl7") (pin "2") (pinfunction "2_2") (pintype "passive"))
      (node (ref "Crl8") (pin "2") (pinfunction "2_2") (pintype "passive"))
      (node (ref "D21") (pin "1") (pinfunction "A_1") (pintype "passive"))
      (node (ref "EX_CON") (pin "5") (pinfunction "5_5") (pintype "passive"))
      (node (ref "ISP") (pin "6") (pinfunction "6_6") (pintype "passive"))
      (node (ref "Q11") (pin "3") (pinfunction "E_3") (pintype "passive"))
      (node (ref "Q12") (pin "3") (pinfunction "E_3") (pintype "passive"))
      (node (ref "Q13") (pin "3") (pinfunction "E_3") (pintype "passive"))
      (node (ref "Q14") (pin "3") (pinfunction "E_3") (pintype "passive"))
      (node (ref "Q15") (pin "3") (pinfunction "E_3") (pintype "passive"))
      (node (ref "Q16") (pin "3") (pinfunction "E_3") (pintype "passive"))
      (node (ref "Q17") (pin "3") (pinfunction "E_3") (pintype "passive"))
      (node (ref "Q18") (pin "3") (pinfunction "E_3") (pintype "passive"))
      (node (ref "R02") (pin "1") (pinfunction "1_1") (pintype "passive"))
      (node (ref "R04") (pin "1") (pinfunction "1_1") (pintype "passive"))
      (node (ref "R06") (pin "1") (pinfunction "1_1") (pintype "passive"))
      (node (ref "R08") (pin "1") (pinfunction "1_1") (pintype "passive"))
      (node (ref "R10") (pin "1") (pinfunction "1_1") (pintype "passive"))
      (node (ref "R12") (pin "1") (pinfunction "1_1") (pintype "passive"))
      (node (ref "R14") (pin "1") (pinfunction "1_1") (pintype "passive"))
      (node (ref "R16") (pin "1") (pinfunction "1_1") (pintype "passive"))
      (node (ref "R21") (pin "2") (pinfunction "2_2") (pintype "passive"))
      (node (ref "Rl52") (pin "1") (pinfunction "1_1") (pintype "passive"))
      (node (ref "Rrl12") (pin "1") (pinfunction "1_1") (pintype "passive"))
      (node (ref "Rrl22") (pin "1") (pinfunction "1_1") (pintype "passive"))
      (node (ref "Rrl32") (pin "1") (pinfunction "1_1") (pintype "passive"))
      (node (ref "Rrl42") (pin "1") (pinfunction "1_1") (pintype "passive"))
      (node (ref "Rrl62") (pin "1") (pinfunction "1_1") (pintype "passive"))
      (node (ref "Rrl72") (pin "1") (pinfunction "1_1") (pintype "passive"))
      (node (ref "Rrl82") (pin "1") (pinfunction "1_1") (pintype "passive"))
      (node (ref "U2") (pin "2") (pintype "passive"))
      (node (ref "U3") (pin "21") (pinfunction "GND_21") (pintype "power_in"))
      (node (ref "U3") (pin "3") (pinfunction "GND_3") (pintype "power_in"))
      (node (ref "U3") (pin "5") (pinfunction "GND_5") (pintype "power_in"))
    )
    (net (code "39") (name "Net-(CON1-Pad1)") (class "Default")
      (node (ref "CON1") (pin "1") (pinfunction "1_1") (pintype "passive"))
      (node (ref "RL1") (pin "2") (pinfunction "2_2") (pintype "passive"))
    )
    (net (code "40") (name "Net-(CON1-Pad2)") (class "Default")
      (node (ref "CON1") (pin "2") (pinfunction "2_2") (pintype "passive"))
      (node (ref "Csub1") (pin "2") (pinfunction "2_2") (pintype "passive"))
      (node (ref "MOV1") (pin "2") (pinfunction "2_2") (pintype "passive"))
      (node (ref "RL1") (pin "1") (pinfunction "1_1") (pintype "passive"))
    )
    (net (code "41") (name "Net-(CON1-Pad3)") (class "Default")
      (node (ref "CON1") (pin "3") (pinfunction "3_3") (pintype "passive"))
      (node (ref "MOV1") (pin "1") (pinfunction "1_1") (pintype "passive"))
      (node (ref "RL1") (pin "3") (pinfunction "3_3") (pintype "passive"))
      (node (ref "Rsub1") (pin "2") (pinfunction "2_2") (pintype "passive"))
    )
    (net (code "42") (name "Net-(CON2-Pad1)") (class "Default")
      (node (ref "CON2") (pin "1") (pinfunction "1_1") (pintype "passive"))
      (node (ref "RL2") (pin "2") (pinfunction "2_2") (pintype "passive"))
    )
    (net (code "43") (name "Net-(CON2-Pad2)") (class "Default")
      (node (ref "CON2") (pin "2") (pinfunction "2_2") (pintype "passive"))
      (node (ref "Csub2") (pin "2") (pinfunction "2_2") (pintype "passive"))
      (node (ref "MOV2") (pin "2") (pinfunction "2_2") (pintype "passive"))
      (node (ref "RL2") (pin "1") (pinfunction "1_1") (pintype "passive"))
    )
    (net (code "44") (name "Net-(CON2-Pad3)") (class "Default")
      (node (ref "CON2") (pin "3") (pinfunction "3_3") (pintype "passive"))
      (node (ref "MOV2") (pin "1") (pinfunction "1_1") (pintype "passive"))
      (node (ref "RL2") (pin "3") (pinfunction "3_3") (pintype "passive"))
      (node (ref "Rsub2") (pin "2") (pinfunction "2_2") (pintype "passive"))
    )
    (net (code "45") (name "Net-(CON3-Pad1)") (class "Default")
      (node (ref "CON3") (pin "1") (pinfunction "1_1") (pintype "passive"))
      (node (ref "RL3") (pin "2") (pinfunction "2_2") (pintype "passive"))
    )
    (net (code "46") (name "Net-(CON3-Pad2)") (class "Default")
      (node (ref "CON3") (pin "2") (pinfunction "2_2") (pintype "passive"))
      (node (ref "Csub3") (pin "2") (pinfunction "2_2") (pintype "passive"))
      (node (ref "MOV3") (pin "2") (pinfunction "2_2") (pintype "passive"))
      (node (ref "RL3") (pin "1") (pinfunction "1_1") (pintype "passive"))
    )
    (net (code "47") (name "Net-(CON3-Pad3)") (class "Default")
      (node (ref "CON3") (pin "3") (pinfunction "3_3") (pintype "passive"))
      (node (ref "MOV3") (pin "1") (pinfunction "1_1") (pintype "passive"))
      (node (ref "RL3") (pin "3") (pinfunction "3_3") (pintype "passive"))
      (node (ref "Rsub3") (pin "2") (pinfunction "2_2") (pintype "passive"))
    )
    (net (code "48") (name "Net-(CON4-Pad1)") (class "Default")
      (node (ref "CON4") (pin "1") (pinfunction "1_1") (pintype "passive"))
      (node (ref "RL4") (pin "2") (pinfunction "2_2") (pintype "passive"))
    )
    (net (code "49") (name "Net-(CON4-Pad2)") (class "Default")
      (node (ref "CON4") (pin "2") (pinfunction "2_2") (pintype "passive"))
      (node (ref "Csub4") (pin "2") (pinfunction "2_2") (pintype "passive"))
      (node (ref "MOV4") (pin "2") (pinfunction "2_2") (pintype "passive"))
      (node (ref "RL4") (pin "1") (pinfunction "1_1") (pintype "passive"))
    )
    (net (code "50") (name "Net-(CON4-Pad3)") (class "Default")
      (node (ref "CON4") (pin "3") (pinfunction "3_3") (pintype "passive"))
      (node (ref "MOV4") (pin "1") (pinfunction "1_1") (pintype "passive"))
      (node (ref "RL4") (pin "3") (pinfunction "3_3") (pintype "passive"))
      (node (ref "Rsub4") (pin "2") (pinfunction "2_2") (pintype "passive"))
    )
    (net (code "51") (name "Net-(CON5-Pad1)") (class "Default")
      (node (ref "CON5") (pin "1") (pinfunction "1_1") (pintype "passive"))
      (node (ref "RL5") (pin "2") (pinfunction "2_2") (pintype "passive"))
    )
    (net (code "52") (name "Net-(CON5-Pad2)") (class "Default")
      (node (ref "CON5") (pin "2") (pinfunction "2_2") (pintype "passive"))
      (node (ref "Csub5") (pin "2") (pinfunction "2_2") (pintype "passive"))
      (node (ref "MOV5") (pin "2") (pinfunction "2_2") (pintype "passive"))
      (node (ref "RL5") (pin "1") (pinfunction "1_1") (pintype "passive"))
    )
    (net (code "53") (name "Net-(CON5-Pad3)") (class "Default")
      (node (ref "CON5") (pin "3") (pinfunction "3_3") (pintype "passive"))
      (node (ref "MOV5") (pin "1") (pinfunction "1_1") (pintype "passive"))
      (node (ref "RL5") (pin "3") (pinfunction "3_3") (pintype "passive"))
      (node (ref "Rsub5") (pin "2") (pinfunction "2_2") (pintype "passive"))
    )
    (net (code "54") (name "Net-(CON6-Pad1)") (class "Default")
      (node (ref "CON6") (pin "1") (pinfunction "1_1") (pintype "passive"))
      (node (ref "RL6") (pin "2") (pinfunction "2_2") (pintype "passive"))
    )
    (net (code "55") (name "Net-(CON6-Pad2)") (class "Default")
      (node (ref "CON6") (pin "2") (pinfunction "2_2") (pintype "passive"))
      (node (ref "Csub6") (pin "2") (pinfunction "2_2") (pintype "passive"))
      (node (ref "MOV6") (pin "2") (pinfunction "2_2") (pintype "passive"))
      (node (ref "RL6") (pin "1") (pinfunction "1_1") (pintype "passive"))
    )
    (net (code "56") (name "Net-(CON6-Pad3)") (class "Default")
      (node (ref "CON6") (pin "3") (pinfunction "3_3") (pintype "passive"))
      (node (ref "MOV6") (pin "1") (pinfunction "1_1") (pintype "passive"))
      (node (ref "RL6") (pin "3") (pinfunction "3_3") (pintype "passive"))
      (node (ref "Rsub6") (pin "2") (pinfunction "2_2") (pintype "passive"))
    )
    (net (code "57") (name "Net-(CON7-Pad1)") (class "Default")
      (node (ref "CON7") (pin "1") (pinfunction "1_1") (pintype "passive"))
      (node (ref "RL7") (pin "2") (pinfunction "2_2") (pintype "passive"))
    )
    (net (code "58") (name "Net-(CON7-Pad2)") (class "Default")
      (node (ref "CON7") (pin "2") (pinfunction "2_2") (pintype "passive"))
      (node (ref "Csub7") (pin "2") (pinfunction "2_2") (pintype "passive"))
      (node (ref "MOV7") (pin "2") (pinfunction "2_2") (pintype "passive"))
      (node (ref "RL7") (pin "1") (pinfunction "1_1") (pintype "passive"))
    )
    (net (code "59") (name "Net-(CON7-Pad3)") (class "Default")
      (node (ref "CON7") (pin "3") (pinfunction "3_3") (pintype "passive"))
      (node (ref "MOV7") (pin "1") (pinfunction "1_1") (pintype "passive"))
      (node (ref "RL7") (pin "3") (pinfunction "3_3") (pintype "passive"))
      (node (ref "Rsub7") (pin "2") (pinfunction "2_2") (pintype "passive"))
    )
    (net (code "60") (name "Net-(CON8-Pad1)") (class "Default")
      (node (ref "CON8") (pin "1") (pinfunction "1_1") (pintype "passive"))
      (node (ref "RL8") (pin "2") (pinfunction "2_2") (pintype "passive"))
    )
    (net (code "61") (name "Net-(CON8-Pad2)") (class "Default")
      (node (ref "CON8") (pin "2") (pinfunction "2_2") (pintype "passive"))
      (node (ref "Csub8") (pin "2") (pinfunction "2_2") (pintype "passive"))
      (node (ref "MOV8") (pin "2") (pinfunction "2_2") (pintype "passive"))
      (node (ref "RL8") (pin "1") (pinfunction "1_1") (pintype "passive"))
    )
    (net (code "62") (name "Net-(CON8-Pad3)") (class "Default")
      (node (ref "CON8") (pin "3") (pinfunction "3_3") (pintype "passive"))
      (node (ref "MOV8") (pin "1") (pinfunction "1_1") (pintype "passive"))
      (node (ref "RL8") (pin "3") (pinfunction "3_3") (pintype "passive"))
      (node (ref "Rsub8") (pin "2") (pinfunction "2_2") (pintype "passive"))
    )
    (net (code "63") (name "Net-(Csub1-Pad1)") (class "Default")
      (node (ref "Csub1") (pin "1") (pinfunction "1_1") (pintype "passive"))
      (node (ref "Rsub1") (pin "1") (pinfunction "1_1") (pintype "passive"))
    )
    (net (code "64") (name "Net-(Csub2-Pad1)") (class "Default")
      (node (ref "Csub2") (pin "1") (pinfunction "1_1") (pintype "passive"))
      (node (ref "Rsub2") (pin "1") (pinfunction "1_1") (pintype "passive"))
    )
    (net (code "65") (name "Net-(Csub3-Pad1)") (class "Default")
      (node (ref "Csub3") (pin "1") (pinfunction "1_1") (pintype "passive"))
      (node (ref "Rsub3") (pin "1") (pinfunction "1_1") (pintype "passive"))
    )
    (net (code "66") (name "Net-(Csub4-Pad1)") (class "Default")
      (node (ref "Csub4") (pin "1") (pinfunction "1_1") (pintype "passive"))
      (node (ref "Rsub4") (pin "1") (pinfunction "1_1") (pintype "passive"))
    )
    (net (code "67") (name "Net-(Csub5-Pad1)") (class "Default")
      (node (ref "Csub5") (pin "1") (pinfunction "1_1") (pintype "passive"))
      (node (ref "Rsub5") (pin "1") (pinfunction "1_1") (pintype "passive"))
    )
    (net (code "68") (name "Net-(Csub6-Pad1)") (class "Default")
      (node (ref "Csub6") (pin "1") (pinfunction "1_1") (pintype "passive"))
      (node (ref "Rsub6") (pin "1") (pinfunction "1_1") (pintype "passive"))
    )
    (net (code "69") (name "Net-(Csub7-Pad1)") (class "Default")
      (node (ref "Csub7") (pin "1") (pinfunction "1_1") (pintype "passive"))
      (node (ref "Rsub7") (pin "1") (pinfunction "1_1") (pintype "passive"))
    )
    (net (code "70") (name "Net-(Csub8-Pad1)") (class "Default")
      (node (ref "Csub8") (pin "1") (pinfunction "1_1") (pintype "passive"))
      (node (ref "Rsub8") (pin "1") (pinfunction "1_1") (pintype "passive"))
    )
    (net (code "71") (name "Net-(D11-A)") (class "Default")
      (node (ref "D11") (pin "1") (pinfunction "A_1") (pintype "passive"))
      (node (ref "E1") (pin "K") (pinfunction "K_K") (pintype "passive"))
      (node (ref "Q11") (pin "2") (pinfunction "C_2") (pintype "passive"))
      (node (ref "RL1") (pin "4") (pinfunction "4_4") (pintype "passive"))
    )
    (net (code "72") (name "Net-(D12-A)") (class "Default")
      (node (ref "D12") (pin "1") (pinfunction "A_1") (pintype "passive"))
      (node (ref "E2") (pin "K") (pinfunction "K_K") (pintype "passive"))
      (node (ref "Q12") (pin "2") (pinfunction "C_2") (pintype "passive"))
      (node (ref "RL2") (pin "4") (pinfunction "4_4") (pintype "passive"))
    )
    (net (code "73") (name "Net-(D13-A)") (class "Default")
      (node (ref "D13") (pin "1") (pinfunction "A_1") (pintype "passive"))
      (node (ref "E3") (pin "K") (pinfunction "K_K") (pintype "passive"))
      (node (ref "Q13") (pin "2") (pinfunction "C_2") (pintype "passive"))
      (node (ref "RL3") (pin "4") (pinfunction "4_4") (pintype "passive"))
    )
    (net (code "74") (name "Net-(D14-A)") (class "Default")
      (node (ref "D14") (pin "1") (pinfunction "A_1") (pintype "passive"))
      (node (ref "E4") (pin "K") (pinfunction "K_K") (pintype "passive"))
      (node (ref "Q14") (pin "2") (pinfunction "C_2") (pintype "passive"))
      (node (ref "RL4") (pin "4") (pinfunction "4_4") (pintype "passive"))
    )
    (net (code "75") (name "Net-(D15-A)") (class "Default")
      (node (ref "D15") (pin "1") (pinfunction "A_1") (pintype "passive"))
      (node (ref "E5") (pin "K") (pinfunction "K_K") (pintype "passive"))
      (node (ref "Q15") (pin "2") (pinfunction "C_2") (pintype "passive"))
      (node (ref "RL5") (pin "4") (pinfunction "4_4") (pintype "passive"))
    )
    (net (code "76") (name "Net-(D16-A)") (class "Default")
      (node (ref "D16") (pin "1") (pinfunction "A_1") (pintype "passive"))
      (node (ref "E6") (pin "K") (pinfunction "K_K") (pintype "passive"))
      (node (ref "Q16") (pin "2") (pinfunction "C_2") (pintype "passive"))
      (node (ref "RL6") (pin "4") (pinfunction "4_4") (pintype "passive"))
    )
    (net (code "77") (name "Net-(D17-A)") (class "Default")
      (node (ref "D17") (pin "1") (pinfunction "A_1") (pintype "passive"))
      (node (ref "E7") (pin "K") (pinfunction "K_K") (pintype "passive"))
      (node (ref "Q17") (pin "2") (pinfunction "C_2") (pintype "passive"))
      (node (ref "RL7") (pin "4") (pinfunction "4_4") (pintype "passive"))
    )
    (net (code "78") (name "Net-(D18-A)") (class "Default")
      (node (ref "D18") (pin "1") (pinfunction "A_1") (pintype "passive"))
      (node (ref "E8") (pin "K") (pinfunction "K_K") (pintype "passive"))
      (node (ref "Q18") (pin "2") (pinfunction "C_2") (pintype "passive"))
      (node (ref "RL8") (pin "4") (pinfunction "4_4") (pintype "passive"))
    )
    (net (code "79") (name "Net-(D21-K)") (class "Default")
      (node (ref "12V_IN") (pin "1") (pinfunction "1_1") (pintype "passive"))
      (node (ref "D21") (pin "2") (pinfunction "K_2") (pintype "passive"))
      (node (ref "F21") (pin "1") (pinfunction "1_1") (pintype "passive"))
    )
    (net (code "80") (name "Net-(E1-PadA)") (class "Default")
      (node (ref "E1") (pin "A") (pinfunction "A_A") (pintype "passive"))
      (node (ref "Rrl13") (pin "1") (pinfunction "1_1") (pintype "passive"))
    )
    (net (code "81") (name "Net-(E2-PadA)") (class "Default")
      (node (ref "E2") (pin "A") (pinfunction "A_A") (pintype "passive"))
      (node (ref "Rrl23") (pin "1") (pinfunction "1_1") (pintype "passive"))
    )
    (net (code "82") (name "Net-(E3-PadA)") (class "Default")
      (node (ref "E3") (pin "A") (pinfunction "A_A") (pintype "passive"))
      (node (ref "Rrl33") (pin "1") (pinfunction "1_1") (pintype "passive"))
    )
    (net (code "83") (name "Net-(E4-PadA)") (class "Default")
      (node (ref "E4") (pin "A") (pinfunction "A_A") (pintype "passive"))
      (node (ref "Rrl43") (pin "1") (pinfunction "1_1") (pintype "passive"))
    )
    (net (code "84") (name "Net-(E5-PadA)") (class "Default")
      (node (ref "E5") (pin "A") (pinfunction "A_A") (pintype "passive"))
      (node (ref "Rrl53") (pin "1") (pinfunction "1_1") (pintype "passive"))
    )
    (net (code "85") (name "Net-(E6-PadA)") (class "Default")
      (node (ref "E6") (pin "A") (pinfunction "A_A") (pintype "passive"))
      (node (ref "Rrl63") (pin "1") (pinfunction "1_1") (pintype "passive"))
    )
    (net (code "86") (name "Net-(E7-PadA)") (class "Default")
      (node (ref "E7") (pin "A") (pinfunction "A_A") (pintype "passive"))
      (node (ref "Rrl73") (pin "1") (pinfunction "1_1") (pintype "passive"))
    )
    (net (code "87") (name "Net-(E8-PadA)") (class "Default")
      (node (ref "E8") (pin "A") (pinfunction "A_A") (pintype "passive"))
      (node (ref "Rrl83") (pin "1") (pinfunction "1_1") (pintype "passive"))
    )
    (net (code "88") (name "Net-(IN1A-A)") (class "Default")
      (node (ref "IN1") (pin "1") (pinfunction "A_1") (pintype "passive"))
      (node (ref "R01") (pin "1") (pinfunction "1_1") (pintype "passive"))
    )
    (net (code "89") (name "Net-(IN2A-A)") (class "Default")
      (node (ref "IN2") (pin "1") (pinfunction "A_1") (pintype "passive"))
      (node (ref "R03") (pin "1") (pinfunction "1_1") (pintype "passive"))
    )
    (net (code "90") (name "Net-(IN3A-A)") (class "Default")
      (node (ref "IN3") (pin "1") (pinfunction "A_1") (pintype "passive"))
      (node (ref "R05") (pin "1") (pinfunction "1_1") (pintype "passive"))
    )
    (net (code "91") (name "Net-(IN4A-A)") (class "Default")
      (node (ref "IN4") (pin "1") (pinfunction "A_1") (pintype "passive"))
      (node (ref "R07") (pin "1") (pinfunction "1_1") (pintype "passive"))
    )
    (net (code "92") (name "Net-(IN5A-A)") (class "Default")
      (node (ref "IN5") (pin "1") (pinfunction "A_1") (pintype "passive"))
      (node (ref "R09") (pin "1") (pinfunction "1_1") (pintype "passive"))
    )
    (net (code "93") (name "Net-(IN6A-A)") (class "Default")
      (node (ref "IN6") (pin "1") (pinfunction "A_1") (pintype "passive"))
      (node (ref "R11") (pin "1") (pinfunction "1_1") (pintype "passive"))
    )
    (net (code "94") (name "Net-(IN7A-A)") (class "Default")
      (node (ref "IN7") (pin "1") (pinfunction "A_1") (pintype "passive"))
      (node (ref "R13") (pin "1") (pinfunction "1_1") (pintype "passive"))
    )
    (net (code "95") (name "Net-(IN8A-A)") (class "Default")
      (node (ref "IN8") (pin "1") (pinfunction "A_1") (pintype "passive"))
      (node (ref "R15") (pin "1") (pinfunction "1_1") (pintype "passive"))
    )
    (net (code "96") (name "Net-(PW-K)") (class "Default")
      (node (ref "PW") (pin "2") (pinfunction "K_2") (pintype "passive"))
      (node (ref "R21") (pin "1") (pinfunction "1_1") (pintype "passive"))
    )
    (net (code "97") (name "Net-(Q11-B)") (class "Default")
      (node (ref "Q11") (pin "1") (pinfunction "B_1") (pintype "passive"))
      (node (ref "Rrl11") (pin "2") (pinfunction "2_2") (pintype "passive"))
      (node (ref "Rrl12") (pin "2") (pinfunction "2_2") (pintype "passive"))
    )
    (net (code "98") (name "Net-(Q12-B)") (class "Default")
      (node (ref "Q12") (pin "1") (pinfunction "B_1") (pintype "passive"))
      (node (ref "Rrl21") (pin "2") (pinfunction "2_2") (pintype "passive"))
      (node (ref "Rrl22") (pin "2") (pinfunction "2_2") (pintype "passive"))
    )
    (net (code "99") (name "Net-(Q13-B)") (class "Default")
      (node (ref "Q13") (pin "1") (pinfunction "B_1") (pintype "passive"))
      (node (ref "Rrl31") (pin "2") (pinfunction "2_2") (pintype "passive"))
      (node (ref "Rrl32") (pin "2") (pinfunction "2_2") (pintype "passive"))
    )
    (net (code "100") (name "Net-(Q14-B)") (class "Default")
      (node (ref "Q14") (pin "1") (pinfunction "B_1") (pintype "passive"))
      (node (ref "Rrl41") (pin "2") (pinfunction "2_2") (pintype "passive"))
      (node (ref "Rrl42") (pin "2") (pinfunction "2_2") (pintype "passive"))
    )
    (net (code "101") (name "Net-(Q15-B)") (class "Default")
      (node (ref "Q15") (pin "1") (pinfunction "B_1") (pintype "passive"))
      (node (ref "Rl52") (pin "2") (pinfunction "2_2") (pintype "passive"))
      (node (ref "Rrl51") (pin "2") (pinfunction "2_2") (pintype "passive"))
    )
    (net (code "102") (name "Net-(Q16-B)") (class "Default")
      (node (ref "Q16") (pin "1") (pinfunction "B_1") (pintype "passive"))
      (node (ref "Rrl61") (pin "2") (pinfunction "2_2") (pintype "passive"))
      (node (ref "Rrl62") (pin "2") (pinfunction "2_2") (pintype "passive"))
    )
    (net (code "103") (name "Net-(Q17-B)") (class "Default")
      (node (ref "Q17") (pin "1") (pinfunction "B_1") (pintype "passive"))
      (node (ref "Rrl71") (pin "2") (pinfunction "2_2") (pintype "passive"))
      (node (ref "Rrl72") (pin "2") (pinfunction "2_2") (pintype "passive"))
    )
    (net (code "104") (name "Net-(Q18-B)") (class "Default")
      (node (ref "Q18") (pin "1") (pinfunction "B_1") (pintype "passive"))
      (node (ref "Rrl81") (pin "2") (pinfunction "2_2") (pintype "passive"))
      (node (ref "Rrl82") (pin "2") (pinfunction "2_2") (pintype "passive"))
    )
  )
)
